# ecu-new.net
KiCad netlist of a schematic drawn in EAGLE
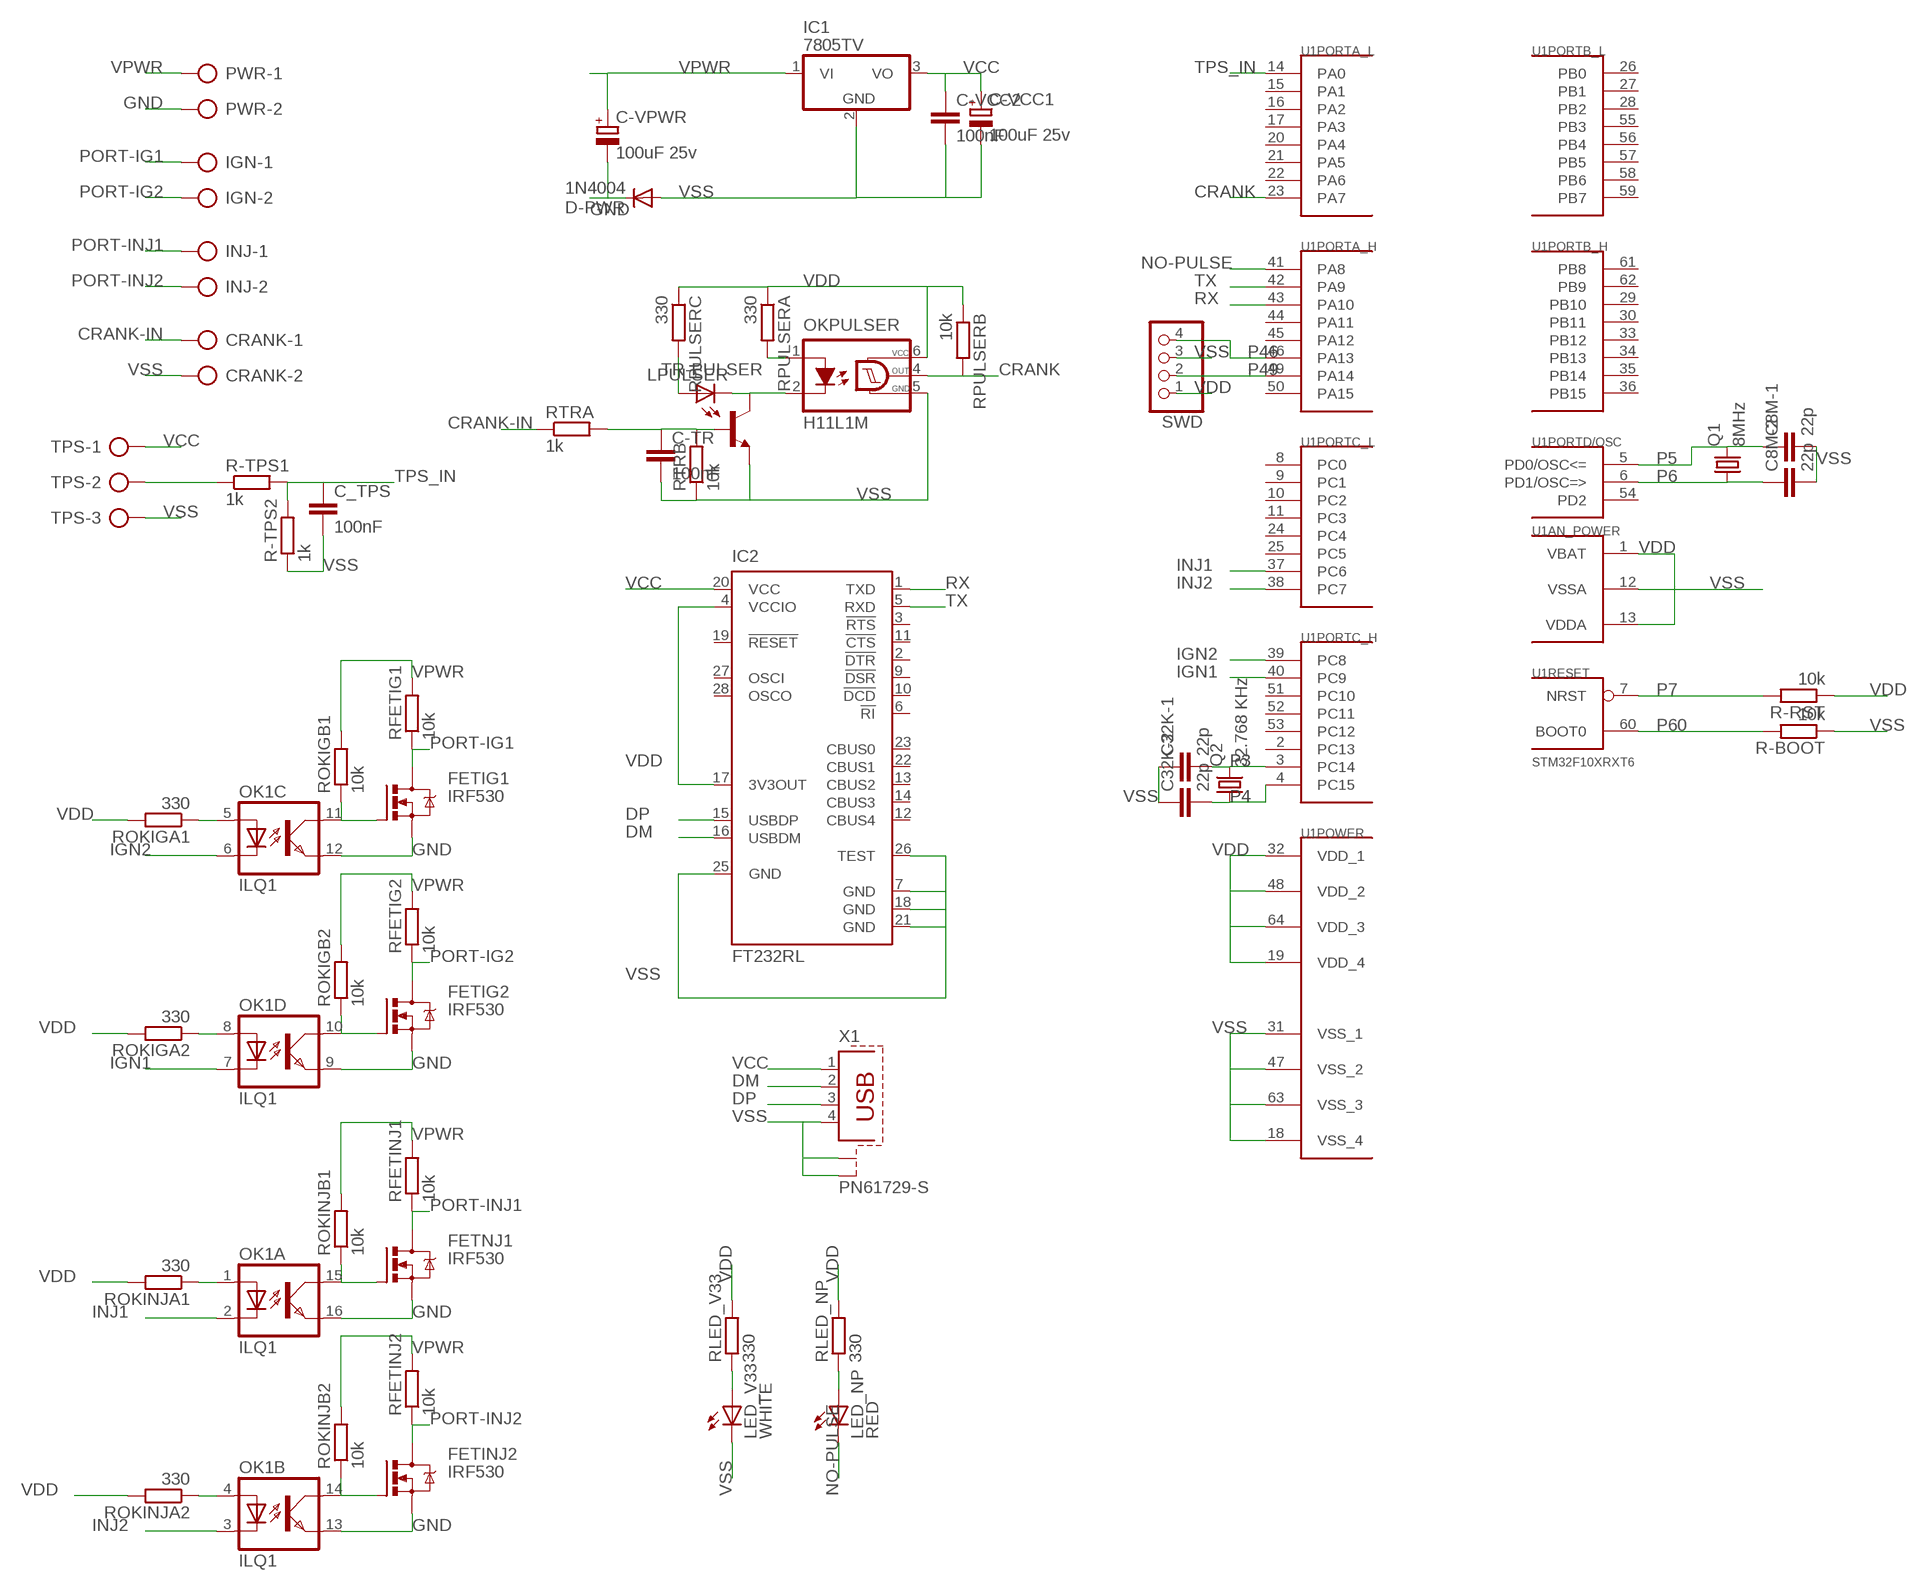
[diagram p0: schematic, sheet 1]

(export (version "E")
  (design (tool "Eeschema 10.0.6"))
  (components
    (comp (ref "C-TR")
      (value "100nF")
      (footprint "eagle-import:C050-024X044")
      (libsource (lib "eagle-import") (part "C-EU050-024X044"))
    )
    (comp (ref "C-VCC1")
      (value "100uF 25v")
      (footprint "eagle-import:E2,5-7")
      (libsource (lib "eagle-import") (part "CPOL-EUE2.5-7"))
    )
    (comp (ref "C-VCC2")
      (value "100nF")
      (footprint "eagle-import:C050-024X044")
      (libsource (lib "eagle-import") (part "C-EU050-024X044"))
    )
    (comp (ref "C-VPWR")
      (value "100uF 25v")
      (footprint "eagle-import:E2,5-7")
      (libsource (lib "eagle-import") (part "CPOL-EUE2.5-7"))
    )
    (comp (ref "C8M-1")
      (value "22p")
      (footprint "eagle-import:C025-030X050")
      (libsource (lib "eagle-import") (part "C-EU025-030X050"))
    )
    (comp (ref "C8M-2")
      (value "22p")
      (footprint "eagle-import:C025-030X050")
      (libsource (lib "eagle-import") (part "C-EU025-030X050"))
    )
    (comp (ref "C32K-1")
      (value "22p")
      (footprint "eagle-import:C025-030X050")
      (libsource (lib "eagle-import") (part "C-EU025-030X050"))
    )
    (comp (ref "C32K-2")
      (value "22p")
      (footprint "eagle-import:C025-030X050")
      (libsource (lib "eagle-import") (part "C-EU025-030X050"))
    )
    (comp (ref "CRANK")
      (value "AK300/2")
      (footprint "eagle-import:AK300_2")
      (libsource (lib "eagle-import") (part "AK300/2"))
    )
    (comp (ref "C_TPS")
      (value "100nF")
      (footprint "eagle-import:C050-024X044")
      (libsource (lib "eagle-import") (part "C-EU050-024X044"))
    )
    (comp (ref "D-PWR")
      (value "1N4004")
      (footprint "eagle-import:DO41-10")
      (libsource (lib "eagle-import") (part "1N4004"))
    )
    (comp (ref "FETIG1")
      (value "IRF530")
      (footprint "eagle-import:TO220BV")
      (libsource (lib "eagle-import") (part "IRF530"))
    )
    (comp (ref "FETIG2")
      (value "IRF530")
      (footprint "eagle-import:TO220BV")
      (libsource (lib "eagle-import") (part "IRF530"))
    )
    (comp (ref "FETINJ2")
      (value "IRF530")
      (footprint "eagle-import:TO220BV")
      (libsource (lib "eagle-import") (part "IRF530"))
    )
    (comp (ref "FETNJ1")
      (value "IRF530")
      (footprint "eagle-import:TO220BV")
      (libsource (lib "eagle-import") (part "IRF530"))
    )
    (comp (ref "IC1")
      (value "7805TV")
      (footprint "eagle-import:TO220V")
      (libsource (lib "eagle-import") (part "78TV05"))
    )
    (comp (ref "IC2")
      (value "FT232RL")
      (footprint "eagle-import:SSOP28")
      (libsource (lib "eagle-import") (part "FT232RL"))
    )
    (comp (ref "IGN")
      (value "AK300/2")
      (footprint "eagle-import:AK300_2")
      (libsource (lib "eagle-import") (part "AK300/2"))
    )
    (comp (ref "INJ")
      (value "AK300/2")
      (footprint "eagle-import:AK300_2")
      (libsource (lib "eagle-import") (part "AK300/2"))
    )
    (comp (ref "LED_NP")
      (value "RED")
      (footprint "eagle-import:LED3MM")
      (libsource (lib "eagle-import") (part "LED3MM"))
    )
    (comp (ref "LED_V33")
      (value "WHITE")
      (footprint "eagle-import:LED3MM")
      (libsource (lib "eagle-import") (part "LED3MM"))
    )
    (comp (ref "LPULSER")
      (value "LED3MM")
      (footprint "eagle-import:LED3MM")
      (libsource (lib "eagle-import") (part "LED3MM"))
    )
    (comp (ref "OK1")
      (value "ILQ1")
      (footprint "eagle-import:DIL16")
      (fields (field (name "MF") "VISHAY/TELEFUNKEN"))
      (libsource (lib "eagle-import") (part "ILQ1"))
    )
    (comp (ref "OKPULSER")
      (value "H11L1M")
      (footprint "eagle-import:DIL06")
      (fields (field (name "MF") "FAIRCHILD SEMICONDUCTOR") (field (name "MPN") "H11L1-M"))
      (libsource (lib "eagle-import") (part "H11LM1"))
    )
    (comp (ref "PWR")
      (value "AK300/2")
      (footprint "eagle-import:AK300_2")
      (libsource (lib "eagle-import") (part "AK300/2"))
    )
    (comp (ref "Q1")
      (value "8MHz")
      (footprint "eagle-import:HC49_S")
      (libsource (lib "eagle-import") (part "CRYSTALHC49S"))
    )
    (comp (ref "Q2")
      (value "32.768 KHz")
      (footprint "eagle-import:TC26H")
      (libsource (lib "eagle-import") (part "CRYSTALTC26H"))
    )
    (comp (ref "R-BOOT")
      (value "10k")
      (footprint "eagle-import:0204_7")
      (libsource (lib "eagle-import") (part "R-EU_0204/7"))
    )
    (comp (ref "R-RST")
      (value "10k")
      (footprint "eagle-import:0204_7")
      (libsource (lib "eagle-import") (part "R-EU_0204/7"))
    )
    (comp (ref "R-TPS1")
      (value "1k")
      (footprint "eagle-import:0204_7")
      (libsource (lib "eagle-import") (part "R-EU_0204/7"))
    )
    (comp (ref "R-TPS2")
      (value "1k")
      (footprint "eagle-import:0204_7")
      (libsource (lib "eagle-import") (part "R-EU_0204/7"))
    )
    (comp (ref "RFETIG1")
      (value "10k")
      (footprint "eagle-import:0204_7")
      (libsource (lib "eagle-import") (part "R-EU_0204/7"))
    )
    (comp (ref "RFETIG2")
      (value "10k")
      (footprint "eagle-import:0204_7")
      (libsource (lib "eagle-import") (part "R-EU_0204/7"))
    )
    (comp (ref "RFETINJ1")
      (value "10k")
      (footprint "eagle-import:0204_7")
      (libsource (lib "eagle-import") (part "R-EU_0204/7"))
    )
    (comp (ref "RFETINJ2")
      (value "10k")
      (footprint "eagle-import:0204_7")
      (libsource (lib "eagle-import") (part "R-EU_0204/7"))
    )
    (comp (ref "RLED_NP")
      (value "330")
      (footprint "eagle-import:0204_7")
      (libsource (lib "eagle-import") (part "R-EU_0204/7"))
    )
    (comp (ref "RLED_V33")
      (value "330")
      (footprint "eagle-import:0204_7")
      (libsource (lib "eagle-import") (part "R-EU_0204/7"))
    )
    (comp (ref "ROKIGA1")
      (value "330")
      (footprint "eagle-import:0204_7")
      (libsource (lib "eagle-import") (part "R-EU_0204/7"))
    )
    (comp (ref "ROKIGA2")
      (value "330")
      (footprint "eagle-import:0204_7")
      (libsource (lib "eagle-import") (part "R-EU_0204/7"))
    )
    (comp (ref "ROKIGB1")
      (value "10k")
      (footprint "eagle-import:0204_7")
      (libsource (lib "eagle-import") (part "R-EU_0204/7"))
    )
    (comp (ref "ROKIGB2")
      (value "10k")
      (footprint "eagle-import:0204_7")
      (libsource (lib "eagle-import") (part "R-EU_0204/7"))
    )
    (comp (ref "ROKINJA1")
      (value "330")
      (footprint "eagle-import:0204_7")
      (libsource (lib "eagle-import") (part "R-EU_0204/7"))
    )
    (comp (ref "ROKINJA2")
      (value "330")
      (footprint "eagle-import:0204_7")
      (libsource (lib "eagle-import") (part "R-EU_0204/7"))
    )
    (comp (ref "ROKINJB1")
      (value "10k")
      (footprint "eagle-import:0204_7")
      (libsource (lib "eagle-import") (part "R-EU_0204/7"))
    )
    (comp (ref "ROKINJB2")
      (value "10k")
      (footprint "eagle-import:0204_7")
      (libsource (lib "eagle-import") (part "R-EU_0204/7"))
    )
    (comp (ref "RPULSERA")
      (value "330")
      (footprint "eagle-import:0204_7")
      (libsource (lib "eagle-import") (part "R-EU_0204/7"))
    )
    (comp (ref "RPULSERB")
      (value "10k")
      (footprint "eagle-import:0204_7")
      (libsource (lib "eagle-import") (part "R-EU_0204/7"))
    )
    (comp (ref "RPULSERC")
      (value "330")
      (footprint "eagle-import:0204_7")
      (libsource (lib "eagle-import") (part "R-EU_0204/7"))
    )
    (comp (ref "RTRA")
      (value "1k")
      (footprint "eagle-import:0204_7")
      (libsource (lib "eagle-import") (part "R-EU_0204/7"))
    )
    (comp (ref "RTRB")
      (value "10k")
      (footprint "eagle-import:0204_7")
      (libsource (lib "eagle-import") (part "R-EU_0204/7"))
    )
    (comp (ref "SWD")
      (value "PINHD-1X4")
      (footprint "eagle-import:1X04")
      (libsource (lib "eagle-import") (part "PINHD-1X4"))
    )
    (comp (ref "TPS")
      (value "AK300/3")
      (footprint "eagle-import:AK300_3")
      (libsource (lib "eagle-import") (part "AK300/3"))
    )
    (comp (ref "TR-PULSER")
      (value "2N3904-NPN-TO92-EBC")
      (footprint "eagle-import:TO92-EBC")
      (libsource (lib "eagle-import") (part "-NPN-TO92-EBC2N3904"))
    )
    (comp (ref "U1")
      (value "STM32F10XRXT6")
      (footprint "eagle-import:TQFP64")
      (libsource (lib "eagle-import") (part "STM32F10XRXT6"))
    )
    (comp (ref "X1")
      (value "PN61729-S")
      (footprint "eagle-import:PN61729-S")
      (libsource (lib "eagle-import") (part "PN61729-S"))
    )
  )
  (nets
    (net (code "1") (name "/CRANK") (class "Default")
      (node (ref "OKPULSER") (pin "4") (pinfunction "OUT_4") (pintype "output"))
      (node (ref "RPULSERB") (pin "2") (pinfunction "2_2") (pintype "passive"))
      (node (ref "U1") (pin "23") (pinfunction "PA7_23") (pintype "bidirectional"))
    )
    (net (code "2") (name "/CRANK-IN") (class "Default")
      (node (ref "CRANK") (pin "1") (pinfunction "KL_1") (pintype "passive"))
      (node (ref "RTRA") (pin "1") (pinfunction "1_1") (pintype "passive"))
    )
    (net (code "3") (name "/DM") (class "Default")
      (node (ref "IC2") (pin "16") (pinfunction "USBDM_16") (pintype "bidirectional"))
      (node (ref "X1") (pin "2") (pinfunction "2_2") (pintype "passive"))
    )
    (net (code "4") (name "/DP") (class "Default")
      (node (ref "IC2") (pin "15") (pinfunction "USBDP_15") (pintype "bidirectional"))
      (node (ref "X1") (pin "3") (pinfunction "3_3") (pintype "passive"))
    )
    (net (code "5") (name "/GND") (class "Default")
      (node (ref "C-VPWR") (pin "-") (pinfunction "-_-") (pintype "passive"))
      (node (ref "D-PWR") (pin "C") (pinfunction "C_C") (pintype "passive"))
      (node (ref "FETIG1") (pin "S") (pinfunction "S_S") (pintype "passive"))
      (node (ref "FETIG2") (pin "S") (pinfunction "S_S") (pintype "passive"))
      (node (ref "FETINJ2") (pin "S") (pinfunction "S_S") (pintype "passive"))
      (node (ref "FETNJ1") (pin "S") (pinfunction "S_S") (pintype "passive"))
      (node (ref "OK1") (pin "12") (pinfunction "EMIT_12") (pintype "passive"))
      (node (ref "OK1") (pin "13") (pinfunction "EMIT_13") (pintype "passive"))
      (node (ref "OK1") (pin "16") (pinfunction "EMIT_16") (pintype "passive"))
      (node (ref "OK1") (pin "9") (pinfunction "EMIT_9") (pintype "passive"))
      (node (ref "PWR") (pin "2") (pinfunction "KL_2") (pintype "passive"))
    )
    (net (code "6") (name "/IGN1") (class "Default")
      (node (ref "OK1") (pin "7") (pinfunction "C_7") (pintype "passive"))
      (node (ref "U1") (pin "40") (pinfunction "PC9_40") (pintype "bidirectional"))
    )
    (net (code "7") (name "/IGN2") (class "Default")
      (node (ref "OK1") (pin "6") (pinfunction "C_6") (pintype "passive"))
      (node (ref "U1") (pin "39") (pinfunction "PC8_39") (pintype "bidirectional"))
    )
    (net (code "8") (name "/INJ1") (class "Default")
      (node (ref "OK1") (pin "2") (pinfunction "C_2") (pintype "passive"))
      (node (ref "U1") (pin "37") (pinfunction "PC6_37") (pintype "bidirectional"))
    )
    (net (code "9") (name "/INJ2") (class "Default")
      (node (ref "OK1") (pin "3") (pinfunction "C_3") (pintype "passive"))
      (node (ref "U1") (pin "38") (pinfunction "PC7_38") (pintype "bidirectional"))
    )
    (net (code "10") (name "/NO-PULSE") (class "Default")
      (node (ref "LED_NP") (pin "K") (pinfunction "C_K") (pintype "passive"))
      (node (ref "U1") (pin "41") (pinfunction "PA8_41") (pintype "bidirectional"))
    )
    (net (code "11") (name "/P3") (class "Default")
      (node (ref "C32K-1") (pin "2") (pinfunction "2_2") (pintype "passive"))
      (node (ref "Q2") (pin "2") (pinfunction "2_2") (pintype "passive"))
      (node (ref "U1") (pin "3") (pinfunction "PC14_3") (pintype "bidirectional"))
    )
    (net (code "12") (name "/P4") (class "Default")
      (node (ref "C32K-2") (pin "2") (pinfunction "2_2") (pintype "passive"))
      (node (ref "Q2") (pin "1") (pinfunction "1_1") (pintype "passive"))
      (node (ref "U1") (pin "4") (pinfunction "PC15_4") (pintype "bidirectional"))
    )
    (net (code "13") (name "/P5") (class "Default")
      (node (ref "C8M-1") (pin "1") (pinfunction "1_1") (pintype "passive"))
      (node (ref "Q1") (pin "2") (pinfunction "2_2") (pintype "passive"))
      (node (ref "U1") (pin "5") (pinfunction "PD0/OSC<=_5") (pintype "bidirectional"))
    )
    (net (code "14") (name "/P6") (class "Default")
      (node (ref "C8M-2") (pin "1") (pinfunction "1_1") (pintype "passive"))
      (node (ref "Q1") (pin "1") (pinfunction "1_1") (pintype "passive"))
      (node (ref "U1") (pin "6") (pinfunction "PD1/OSC=>_6") (pintype "bidirectional"))
    )
    (net (code "15") (name "/P7") (class "Default")
      (node (ref "R-RST") (pin "2") (pinfunction "2_2") (pintype "passive"))
      (node (ref "U1") (pin "7") (pinfunction "NRST_7") (pintype "input"))
    )
    (net (code "16") (name "/P46") (class "Default")
      (node (ref "SWD") (pin "4") (pinfunction "4_4") (pintype "passive"))
      (node (ref "U1") (pin "46") (pinfunction "PA13_46") (pintype "bidirectional"))
    )
    (net (code "17") (name "/P49") (class "Default")
      (node (ref "SWD") (pin "2") (pinfunction "2_2") (pintype "passive"))
      (node (ref "U1") (pin "49") (pinfunction "PA14_49") (pintype "bidirectional"))
    )
    (net (code "18") (name "/P60") (class "Default")
      (node (ref "R-BOOT") (pin "2") (pinfunction "2_2") (pintype "passive"))
      (node (ref "U1") (pin "60") (pinfunction "BOOT0_60") (pintype "input"))
    )
    (net (code "19") (name "/PORT-IG1") (class "Default")
      (node (ref "FETIG1") (pin "D") (pinfunction "D_D") (pintype "passive"))
      (node (ref "IGN") (pin "1") (pinfunction "KL_1") (pintype "passive"))
      (node (ref "RFETIG1") (pin "1") (pinfunction "1_1") (pintype "passive"))
    )
    (net (code "20") (name "/PORT-IG2") (class "Default")
      (node (ref "FETIG2") (pin "D") (pinfunction "D_D") (pintype "passive"))
      (node (ref "IGN") (pin "2") (pinfunction "KL_2") (pintype "passive"))
      (node (ref "RFETIG2") (pin "1") (pinfunction "1_1") (pintype "passive"))
    )
    (net (code "21") (name "/PORT-INJ1") (class "Default")
      (node (ref "FETNJ1") (pin "D") (pinfunction "D_D") (pintype "passive"))
      (node (ref "INJ") (pin "1") (pinfunction "KL_1") (pintype "passive"))
      (node (ref "RFETINJ1") (pin "1") (pinfunction "1_1") (pintype "passive"))
    )
    (net (code "22") (name "/PORT-INJ2") (class "Default")
      (node (ref "FETINJ2") (pin "D") (pinfunction "D_D") (pintype "passive"))
      (node (ref "INJ") (pin "2") (pinfunction "KL_2") (pintype "passive"))
      (node (ref "RFETINJ2") (pin "1") (pinfunction "1_1") (pintype "passive"))
    )
    (net (code "23") (name "/RX") (class "Default")
      (node (ref "IC2") (pin "1") (pinfunction "TXD_1") (pintype "output"))
      (node (ref "U1") (pin "43") (pinfunction "PA10_43") (pintype "bidirectional"))
    )
    (net (code "24") (name "/TPS_IN") (class "Default")
      (node (ref "C_TPS") (pin "1") (pinfunction "1_1") (pintype "passive"))
      (node (ref "R-TPS1") (pin "2") (pinfunction "2_2") (pintype "passive"))
      (node (ref "R-TPS2") (pin "2") (pinfunction "2_2") (pintype "passive"))
      (node (ref "U1") (pin "14") (pinfunction "PA0_14") (pintype "bidirectional"))
    )
    (net (code "25") (name "/TX") (class "Default")
      (node (ref "IC2") (pin "5") (pinfunction "RXD_5") (pintype "input"))
      (node (ref "U1") (pin "42") (pinfunction "PA9_42") (pintype "bidirectional"))
    )
    (net (code "26") (name "/VCC") (class "Default")
      (node (ref "C-VCC1") (pin "+") (pinfunction "+_+") (pintype "passive"))
      (node (ref "C-VCC2") (pin "1") (pinfunction "1_1") (pintype "passive"))
      (node (ref "IC1") (pin "3") (pinfunction "VO_3") (pintype "passive"))
      (node (ref "IC2") (pin "20") (pinfunction "VCC_20") (pintype "power_in"))
      (node (ref "TPS") (pin "1") (pinfunction "KL_1") (pintype "passive"))
      (node (ref "X1") (pin "1") (pinfunction "1_1") (pintype "passive"))
    )
    (net (code "27") (name "/VDD") (class "Default")
      (node (ref "IC2") (pin "17") (pinfunction "3V3OUT_17") (pintype "output"))
      (node (ref "IC2") (pin "4") (pinfunction "VCCIO_4") (pintype "power_in"))
      (node (ref "OKPULSER") (pin "6") (pinfunction "VCC_6") (pintype "power_in"))
      (node (ref "R-RST") (pin "1") (pinfunction "1_1") (pintype "passive"))
      (node (ref "RLED_NP") (pin "2") (pinfunction "2_2") (pintype "passive"))
      (node (ref "RLED_V33") (pin "2") (pinfunction "2_2") (pintype "passive"))
      (node (ref "ROKIGA1") (pin "2") (pinfunction "2_2") (pintype "passive"))
      (node (ref "ROKIGA2") (pin "2") (pinfunction "2_2") (pintype "passive"))
      (node (ref "ROKINJA1") (pin "2") (pinfunction "2_2") (pintype "passive"))
      (node (ref "ROKINJA2") (pin "2") (pinfunction "2_2") (pintype "passive"))
      (node (ref "RPULSERA") (pin "1") (pinfunction "1_1") (pintype "passive"))
      (node (ref "RPULSERB") (pin "1") (pinfunction "1_1") (pintype "passive"))
      (node (ref "RPULSERC") (pin "1") (pinfunction "1_1") (pintype "passive"))
      (node (ref "SWD") (pin "1") (pinfunction "1_1") (pintype "passive"))
      (node (ref "U1") (pin "1") (pinfunction "VBAT_1") (pintype "power_in"))
      (node (ref "U1") (pin "13") (pinfunction "VDDA_13") (pintype "power_in"))
      (node (ref "U1") (pin "19") (pinfunction "VDD_4_19") (pintype "power_in"))
      (node (ref "U1") (pin "32") (pinfunction "VDD_1_32") (pintype "power_in"))
      (node (ref "U1") (pin "48") (pinfunction "VDD_2_48") (pintype "power_in"))
      (node (ref "U1") (pin "64") (pinfunction "VDD_3_64") (pintype "power_in"))
    )
    (net (code "28") (name "/VPWR") (class "Default")
      (node (ref "C-VPWR") (pin "+") (pinfunction "+_+") (pintype "passive"))
      (node (ref "IC1") (pin "1") (pinfunction "VI_1") (pintype "input"))
      (node (ref "PWR") (pin "1") (pinfunction "KL_1") (pintype "passive"))
      (node (ref "RFETIG1") (pin "2") (pinfunction "2_2") (pintype "passive"))
      (node (ref "RFETIG2") (pin "2") (pinfunction "2_2") (pintype "passive"))
      (node (ref "RFETINJ1") (pin "2") (pinfunction "2_2") (pintype "passive"))
      (node (ref "RFETINJ2") (pin "2") (pinfunction "2_2") (pintype "passive"))
      (node (ref "ROKIGB1") (pin "2") (pinfunction "2_2") (pintype "passive"))
      (node (ref "ROKIGB2") (pin "2") (pinfunction "2_2") (pintype "passive"))
      (node (ref "ROKINJB1") (pin "2") (pinfunction "2_2") (pintype "passive"))
      (node (ref "ROKINJB2") (pin "2") (pinfunction "2_2") (pintype "passive"))
    )
    (net (code "29") (name "/VSS") (class "Default")
      (node (ref "C-TR") (pin "2") (pinfunction "2_2") (pintype "passive"))
      (node (ref "C-VCC1") (pin "-") (pinfunction "-_-") (pintype "passive"))
      (node (ref "C-VCC2") (pin "2") (pinfunction "2_2") (pintype "passive"))
      (node (ref "C32K-1") (pin "1") (pinfunction "1_1") (pintype "passive"))
      (node (ref "C32K-2") (pin "1") (pinfunction "1_1") (pintype "passive"))
      (node (ref "C8M-1") (pin "2") (pinfunction "2_2") (pintype "passive"))
      (node (ref "C8M-2") (pin "2") (pinfunction "2_2") (pintype "passive"))
      (node (ref "CRANK") (pin "2") (pinfunction "KL_2") (pintype "passive"))
      (node (ref "C_TPS") (pin "2") (pinfunction "2_2") (pintype "passive"))
      (node (ref "D-PWR") (pin "A") (pinfunction "A_A") (pintype "passive"))
      (node (ref "IC1") (pin "2") (pinfunction "GND_2") (pintype "passive"))
      (node (ref "IC2") (pin "18") (pinfunction "GND_18") (pintype "power_in"))
      (node (ref "IC2") (pin "21") (pinfunction "GND_21") (pintype "power_in"))
      (node (ref "IC2") (pin "25") (pinfunction "GND_25") (pintype "power_in"))
      (node (ref "IC2") (pin "26") (pinfunction "TEST_26") (pintype "input"))
      (node (ref "IC2") (pin "7") (pinfunction "GND_7") (pintype "power_in"))
      (node (ref "LED_V33") (pin "K") (pinfunction "C_K") (pintype "passive"))
      (node (ref "OKPULSER") (pin "5") (pinfunction "GND_5") (pintype "power_in"))
      (node (ref "R-BOOT") (pin "1") (pinfunction "1_1") (pintype "passive"))
      (node (ref "R-TPS2") (pin "1") (pinfunction "1_1") (pintype "passive"))
      (node (ref "RTRB") (pin "1") (pinfunction "1_1") (pintype "passive"))
      (node (ref "SWD") (pin "3") (pinfunction "3_3") (pintype "passive"))
      (node (ref "TPS") (pin "3") (pinfunction "KL_3") (pintype "passive"))
      (node (ref "TR-PULSER") (pin "E") (pinfunction "E_E") (pintype "passive"))
      (node (ref "U1") (pin "12") (pinfunction "VSSA_12") (pintype "power_in"))
      (node (ref "U1") (pin "18") (pinfunction "VSS_4_18") (pintype "power_in"))
      (node (ref "U1") (pin "31") (pinfunction "VSS_1_31") (pintype "power_in"))
      (node (ref "U1") (pin "47") (pinfunction "VSS_2_47") (pintype "power_in"))
      (node (ref "U1") (pin "63") (pinfunction "VSS_3_63") (pintype "power_in"))
      (node (ref "X1") (pin "4") (pinfunction "4_4") (pintype "passive"))
      (node (ref "X1") (pin "S1") (pinfunction "S1_S1") (pintype "passive"))
      (node (ref "X1") (pin "S2") (pinfunction "S2_S2") (pintype "passive"))
    )
    (net (code "30") (name "Net-(C-TR-Pad1)") (class "Default")
      (node (ref "C-TR") (pin "1") (pinfunction "1_1") (pintype "passive"))
      (node (ref "RTRA") (pin "2") (pinfunction "2_2") (pintype "passive"))
      (node (ref "RTRB") (pin "2") (pinfunction "2_2") (pintype "passive"))
      (node (ref "TR-PULSER") (pin "B") (pinfunction "B_B") (pintype "passive"))
    )
    (net (code "31") (name "Net-(LED_NP-PadA)") (class "Default")
      (node (ref "LED_NP") (pin "A") (pinfunction "A_A") (pintype "passive"))
      (node (ref "RLED_NP") (pin "1") (pinfunction "1_1") (pintype "passive"))
    )
    (net (code "32") (name "Net-(LED_V33-PadA)") (class "Default")
      (node (ref "LED_V33") (pin "A") (pinfunction "A_A") (pintype "passive"))
      (node (ref "RLED_V33") (pin "1") (pinfunction "1_1") (pintype "passive"))
    )
    (net (code "33") (name "Net-(LPULSER-C)") (class "Default")
      (node (ref "LPULSER") (pin "K") (pinfunction "C_K") (pintype "passive"))
      (node (ref "OKPULSER") (pin "2") (pinfunction "C_2") (pintype "passive"))
      (node (ref "TR-PULSER") (pin "C") (pinfunction "C_C") (pintype "passive"))
    )
    (net (code "34") (name "Net-(LPULSER-PadA)") (class "Default")
      (node (ref "LPULSER") (pin "A") (pinfunction "A_A") (pintype "passive"))
      (node (ref "RPULSERC") (pin "2") (pinfunction "2_2") (pintype "passive"))
    )
    (net (code "35") (name "Net-(OK1A-A)") (class "Default")
      (node (ref "OK1") (pin "1") (pinfunction "A_1") (pintype "passive"))
      (node (ref "ROKINJA1") (pin "1") (pinfunction "1_1") (pintype "passive"))
    )
    (net (code "36") (name "Net-(OK1A-COL)") (class "Default")
      (node (ref "FETNJ1") (pin "G") (pinfunction "G_G") (pintype "passive"))
      (node (ref "OK1") (pin "15") (pinfunction "COL_15") (pintype "passive"))
      (node (ref "ROKINJB1") (pin "1") (pinfunction "1_1") (pintype "passive"))
    )
    (net (code "37") (name "Net-(OK1B-A)") (class "Default")
      (node (ref "OK1") (pin "4") (pinfunction "A_4") (pintype "passive"))
      (node (ref "ROKINJA2") (pin "1") (pinfunction "1_1") (pintype "passive"))
    )
    (net (code "38") (name "Net-(OK1B-COL)") (class "Default")
      (node (ref "FETINJ2") (pin "G") (pinfunction "G_G") (pintype "passive"))
      (node (ref "OK1") (pin "14") (pinfunction "COL_14") (pintype "passive"))
      (node (ref "ROKINJB2") (pin "1") (pinfunction "1_1") (pintype "passive"))
    )
    (net (code "39") (name "Net-(OK1C-A)") (class "Default")
      (node (ref "OK1") (pin "5") (pinfunction "A_5") (pintype "passive"))
      (node (ref "ROKIGA1") (pin "1") (pinfunction "1_1") (pintype "passive"))
    )
    (net (code "40") (name "Net-(OK1C-COL)") (class "Default")
      (node (ref "FETIG1") (pin "G") (pinfunction "G_G") (pintype "passive"))
      (node (ref "OK1") (pin "11") (pinfunction "COL_11") (pintype "passive"))
      (node (ref "ROKIGB1") (pin "1") (pinfunction "1_1") (pintype "passive"))
    )
    (net (code "41") (name "Net-(OK1D-A)") (class "Default")
      (node (ref "OK1") (pin "8") (pinfunction "A_8") (pintype "passive"))
      (node (ref "ROKIGA2") (pin "1") (pinfunction "1_1") (pintype "passive"))
    )
    (net (code "42") (name "Net-(OK1D-COL)") (class "Default")
      (node (ref "FETIG2") (pin "G") (pinfunction "G_G") (pintype "passive"))
      (node (ref "OK1") (pin "10") (pinfunction "COL_10") (pintype "passive"))
      (node (ref "ROKIGB2") (pin "1") (pinfunction "1_1") (pintype "passive"))
    )
    (net (code "43") (name "Net-(OKPULSER-A)") (class "Default")
      (node (ref "OKPULSER") (pin "1") (pinfunction "A_1") (pintype "passive"))
      (node (ref "RPULSERA") (pin "2") (pinfunction "2_2") (pintype "passive"))
    )
    (net (code "44") (name "Net-(TPSB-KL)") (class "Default")
      (node (ref "R-TPS1") (pin "1") (pinfunction "1_1") (pintype "passive"))
      (node (ref "TPS") (pin "2") (pinfunction "KL_2") (pintype "passive"))
    )
    (net (code "45") (name "unconnected-(IC2-CBUS0-Pad23)") (class "Default")
      (node (ref "IC2") (pin "23") (pinfunction "CBUS0_23") (pintype "bidirectional"))
    )
    (net (code "46") (name "unconnected-(IC2-CBUS1-Pad22)") (class "Default")
      (node (ref "IC2") (pin "22") (pinfunction "CBUS1_22") (pintype "bidirectional"))
    )
    (net (code "47") (name "unconnected-(IC2-CBUS2-Pad13)") (class "Default")
      (node (ref "IC2") (pin "13") (pinfunction "CBUS2_13") (pintype "bidirectional"))
    )
    (net (code "48") (name "unconnected-(IC2-CBUS3-Pad14)") (class "Default")
      (node (ref "IC2") (pin "14") (pinfunction "CBUS3_14") (pintype "bidirectional"))
    )
    (net (code "49") (name "unconnected-(IC2-CBUS4-Pad12)") (class "Default")
      (node (ref "IC2") (pin "12") (pinfunction "CBUS4_12") (pintype "bidirectional"))
    )
    (net (code "50") (name "unconnected-(IC2-OSCI-Pad27)") (class "Default")
      (node (ref "IC2") (pin "27") (pinfunction "OSCI_27") (pintype "input"))
    )
    (net (code "51") (name "unconnected-(IC2-OSCO-Pad28)") (class "Default")
      (node (ref "IC2") (pin "28") (pinfunction "OSCO_28") (pintype "output"))
    )
    (net (code "52") (name "unconnected-(IC2-~{CTS}-Pad11)") (class "Default")
      (node (ref "IC2") (pin "11") (pinfunction "~{CTS}_11") (pintype "input"))
    )
    (net (code "53") (name "unconnected-(IC2-~{DCD}-Pad10)") (class "Default")
      (node (ref "IC2") (pin "10") (pinfunction "~{DCD}_10") (pintype "input"))
    )
    (net (code "54") (name "unconnected-(IC2-~{DSR}-Pad9)") (class "Default")
      (node (ref "IC2") (pin "9") (pinfunction "~{DSR}_9") (pintype "input"))
    )
    (net (code "55") (name "unconnected-(IC2-~{DTR}-Pad2)") (class "Default")
      (node (ref "IC2") (pin "2") (pinfunction "~{DTR}_2") (pintype "output"))
    )
    (net (code "56") (name "unconnected-(IC2-~{RESET}-Pad19)") (class "Default")
      (node (ref "IC2") (pin "19") (pinfunction "~{RESET}_19") (pintype "input"))
    )
    (net (code "57") (name "unconnected-(IC2-~{RI}-Pad6)") (class "Default")
      (node (ref "IC2") (pin "6") (pinfunction "~{RI}_6") (pintype "input"))
    )
    (net (code "58") (name "unconnected-(IC2-~{RTS}-Pad3)") (class "Default")
      (node (ref "IC2") (pin "3") (pinfunction "~{RTS}_3") (pintype "output"))
    )
    (net (code "59") (name "unconnected-(U1B-PA11-Pad44)") (class "Default")
      (node (ref "U1") (pin "44") (pinfunction "PA11_44") (pintype "bidirectional"))
    )
    (net (code "60") (name "unconnected-(U1B-PA12-Pad45)") (class "Default")
      (node (ref "U1") (pin "45") (pinfunction "PA12_45") (pintype "bidirectional"))
    )
    (net (code "61") (name "unconnected-(U1B-PA15-Pad50)") (class "Default")
      (node (ref "U1") (pin "50") (pinfunction "PA15_50") (pintype "bidirectional"))
    )
    (net (code "62") (name "unconnected-(U1C-PA1-Pad15)") (class "Default")
      (node (ref "U1") (pin "15") (pinfunction "PA1_15") (pintype "bidirectional"))
    )
    (net (code "63") (name "unconnected-(U1C-PA2-Pad16)") (class "Default")
      (node (ref "U1") (pin "16") (pinfunction "PA2_16") (pintype "bidirectional"))
    )
    (net (code "64") (name "unconnected-(U1C-PA3-Pad17)") (class "Default")
      (node (ref "U1") (pin "17") (pinfunction "PA3_17") (pintype "bidirectional"))
    )
    (net (code "65") (name "unconnected-(U1C-PA4-Pad20)") (class "Default")
      (node (ref "U1") (pin "20") (pinfunction "PA4_20") (pintype "bidirectional"))
    )
    (net (code "66") (name "unconnected-(U1C-PA5-Pad21)") (class "Default")
      (node (ref "U1") (pin "21") (pinfunction "PA5_21") (pintype "bidirectional"))
    )
    (net (code "67") (name "unconnected-(U1C-PA6-Pad22)") (class "Default")
      (node (ref "U1") (pin "22") (pinfunction "PA6_22") (pintype "bidirectional"))
    )
    (net (code "68") (name "unconnected-(U1D-PB8-Pad61)") (class "Default")
      (node (ref "U1") (pin "61") (pinfunction "PB8_61") (pintype "bidirectional"))
    )
    (net (code "69") (name "unconnected-(U1D-PB9-Pad62)") (class "Default")
      (node (ref "U1") (pin "62") (pinfunction "PB9_62") (pintype "bidirectional"))
    )
    (net (code "70") (name "unconnected-(U1D-PB10-Pad29)") (class "Default")
      (node (ref "U1") (pin "29") (pinfunction "PB10_29") (pintype "bidirectional"))
    )
    (net (code "71") (name "unconnected-(U1D-PB11-Pad30)") (class "Default")
      (node (ref "U1") (pin "30") (pinfunction "PB11_30") (pintype "bidirectional"))
    )
    (net (code "72") (name "unconnected-(U1D-PB12-Pad33)") (class "Default")
      (node (ref "U1") (pin "33") (pinfunction "PB12_33") (pintype "bidirectional"))
    )
    (net (code "73") (name "unconnected-(U1D-PB13-Pad34)") (class "Default")
      (node (ref "U1") (pin "34") (pinfunction "PB13_34") (pintype "bidirectional"))
    )
    (net (code "74") (name "unconnected-(U1D-PB14-Pad35)") (class "Default")
      (node (ref "U1") (pin "35") (pinfunction "PB14_35") (pintype "bidirectional"))
    )
    (net (code "75") (name "unconnected-(U1D-PB15-Pad36)") (class "Default")
      (node (ref "U1") (pin "36") (pinfunction "PB15_36") (pintype "bidirectional"))
    )
    (net (code "76") (name "unconnected-(U1E-PB0-Pad26)") (class "Default")
      (node (ref "U1") (pin "26") (pinfunction "PB0_26") (pintype "bidirectional"))
    )
    (net (code "77") (name "unconnected-(U1E-PB1-Pad27)") (class "Default")
      (node (ref "U1") (pin "27") (pinfunction "PB1_27") (pintype "bidirectional"))
    )
    (net (code "78") (name "unconnected-(U1E-PB2-Pad28)") (class "Default")
      (node (ref "U1") (pin "28") (pinfunction "PB2_28") (pintype "bidirectional"))
    )
    (net (code "79") (name "unconnected-(U1E-PB3-Pad55)") (class "Default")
      (node (ref "U1") (pin "55") (pinfunction "PB3_55") (pintype "bidirectional"))
    )
    (net (code "80") (name "unconnected-(U1E-PB4-Pad56)") (class "Default")
      (node (ref "U1") (pin "56") (pinfunction "PB4_56") (pintype "bidirectional"))
    )
    (net (code "81") (name "unconnected-(U1E-PB5-Pad57)") (class "Default")
      (node (ref "U1") (pin "57") (pinfunction "PB5_57") (pintype "bidirectional"))
    )
    (net (code "82") (name "unconnected-(U1E-PB6-Pad58)") (class "Default")
      (node (ref "U1") (pin "58") (pinfunction "PB6_58") (pintype "bidirectional"))
    )
    (net (code "83") (name "unconnected-(U1E-PB7-Pad59)") (class "Default")
      (node (ref "U1") (pin "59") (pinfunction "PB7_59") (pintype "bidirectional"))
    )
    (net (code "84") (name "unconnected-(U1F-PC10-Pad51)") (class "Default")
      (node (ref "U1") (pin "51") (pinfunction "PC10_51") (pintype "bidirectional"))
    )
    (net (code "85") (name "unconnected-(U1F-PC11-Pad52)") (class "Default")
      (node (ref "U1") (pin "52") (pinfunction "PC11_52") (pintype "bidirectional"))
    )
    (net (code "86") (name "unconnected-(U1F-PC12-Pad53)") (class "Default")
      (node (ref "U1") (pin "53") (pinfunction "PC12_53") (pintype "bidirectional"))
    )
    (net (code "87") (name "unconnected-(U1F-PC13-Pad2)") (class "Default")
      (node (ref "U1") (pin "2") (pinfunction "PC13_2") (pintype "bidirectional"))
    )
    (net (code "88") (name "unconnected-(U1G-PC0-Pad8)") (class "Default")
      (node (ref "U1") (pin "8") (pinfunction "PC0_8") (pintype "bidirectional"))
    )
    (net (code "89") (name "unconnected-(U1G-PC1-Pad9)") (class "Default")
      (node (ref "U1") (pin "9") (pinfunction "PC1_9") (pintype "bidirectional"))
    )
    (net (code "90") (name "unconnected-(U1G-PC2-Pad10)") (class "Default")
      (node (ref "U1") (pin "10") (pinfunction "PC2_10") (pintype "bidirectional"))
    )
    (net (code "91") (name "unconnected-(U1G-PC3-Pad11)") (class "Default")
      (node (ref "U1") (pin "11") (pinfunction "PC3_11") (pintype "bidirectional"))
    )
    (net (code "92") (name "unconnected-(U1G-PC4-Pad24)") (class "Default")
      (node (ref "U1") (pin "24") (pinfunction "PC4_24") (pintype "bidirectional"))
    )
    (net (code "93") (name "unconnected-(U1G-PC5-Pad25)") (class "Default")
      (node (ref "U1") (pin "25") (pinfunction "PC5_25") (pintype "bidirectional"))
    )
    (net (code "94") (name "unconnected-(U1H-PD2-Pad54)") (class "Default")
      (node (ref "U1") (pin "54") (pinfunction "PD2_54") (pintype "bidirectional"))
    )
  )
)
